# PV_Shutdown_2.net
KiCad netlist of a schematic drawn in Altium Designer
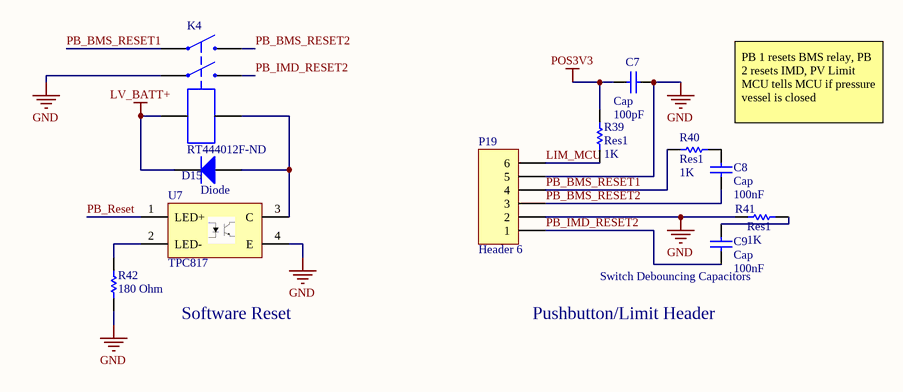
[diagram p0: PV_Shutdown_2.SchDoc]

(export (version "E")
  (design (tool "Eeschema 10.0.6"))
  (components
    (comp (ref "C7")
      (value "Cap")
      (footprint "1206")
      (description "Capacitor")
      (fields (field (name "ALTIUM_VALUE") "100pF") (field (name "PUBLISHER") "Altium Limited"))
      (libsource (lib "Miscellaneous Devices") (part "Cap"))
    )
    (comp (ref "C8")
      (value "Cap")
      (footprint "1206")
      (description "Capacitor")
      (fields (field (name "ALTIUM_VALUE") "100nF") (field (name "PUBLISHER") "Altium Limited"))
      (libsource (lib "Miscellaneous Devices") (part "Cap"))
    )
    (comp (ref "C9")
      (value "Cap")
      (footprint "1206")
      (description "Capacitor")
      (fields (field (name "ALTIUM_VALUE") "100nF") (field (name "PUBLISHER") "Altium Limited"))
      (libsource (lib "Miscellaneous Devices") (part "Cap"))
    )
    (comp (ref "D15")
      (value "Diode")
      (footprint "1N4007")
      (description "Default Diode")
      (fields (field (name "PUBLISHER") "Altium Limited"))
      (libsource (lib "Miscellaneous Devices") (part "Diode"))
    )
    (comp (ref "K4")
      (value "RT444012F-ND")
      (footprint "RT444012F")
      (description "RELAY GEN PURPOSE DPST 8A 12V")
      (libsource (lib "ic") (part "RT444012F-ND"))
    )
    (comp (ref "P19")
      (value "Header 6")
      (footprint "6POS TERM BLOCK")
      (description "Header, 6-Pin")
      (fields (field (name "PUBLISHER") "Altium Limited"))
      (libsource (lib "Miscellaneous Connectors") (part "Header 6"))
    )
    (comp (ref "R39")
      (value "Res1")
      (footprint "1206")
      (description "Resistor")
      (fields (field (name "ALTIUM_VALUE") "1K") (field (name "PUBLISHER") "Altium Limited"))
      (libsource (lib "Miscellaneous Devices") (part "Res1"))
    )
    (comp (ref "R40")
      (value "Res1")
      (footprint "1206")
      (description "Resistor")
      (fields (field (name "ALTIUM_VALUE") "1K") (field (name "PUBLISHER") "Altium Limited"))
      (libsource (lib "Miscellaneous Devices") (part "Res1"))
    )
    (comp (ref "R41")
      (value "Res1")
      (footprint "1206")
      (description "Resistor")
      (fields (field (name "ALTIUM_VALUE") "1K") (field (name "PUBLISHER") "Altium Limited"))
      (libsource (lib "Miscellaneous Devices") (part "Res1"))
    )
    (comp (ref "R42")
      (value "180 Ohm")
      (footprint "1206")
      (description "Resistor")
      (fields (field (name "Comment") "Res1") (field (name "PUBLISHER") "Altium Limited"))
      (libsource (lib "Miscellaneous Devices") (part "Res1"))
    )
    (comp (ref "U7")
      (value "TPC817")
      (footprint "4-SOP")
      (description "Opto-Coupler")
      (libsource (lib "ic") (part "TPC817"))
    )
  )
  (nets
    (net (code "1") (name "/LIM_MCU") (class "Default")
      (node (ref "P19") (pin "6") (pinfunction "6_6") (pintype "passive"))
      (node (ref "R39") (pin "1") (pinfunction "1_1") (pintype "passive"))
    )
    (net (code "2") (name "/PB_BMS_RESET1") (class "Default")
      (node (ref "K4") (pin "5") (pinfunction "5_5") (pintype "passive"))
      (node (ref "P19") (pin "4") (pinfunction "4_4") (pintype "passive"))
      (node (ref "R40") (pin "1") (pinfunction "1_1") (pintype "passive"))
    )
    (net (code "3") (name "/PB_BMS_RESET2") (class "Default")
      (node (ref "C8") (pin "1") (pinfunction "1_1") (pintype "passive"))
      (node (ref "K4") (pin "6") (pinfunction "6_6") (pintype "passive"))
      (node (ref "P19") (pin "3") (pinfunction "3_3") (pintype "passive"))
    )
    (net (code "4") (name "/PB_IMD_RESET2") (class "Default")
      (node (ref "C9") (pin "1") (pinfunction "1_1") (pintype "passive"))
      (node (ref "K4") (pin "4") (pinfunction "4_4") (pintype "passive"))
      (node (ref "P19") (pin "1") (pinfunction "1_1") (pintype "passive"))
    )
    (net (code "5") (name "/PB_Reset") (class "Default")
      (node (ref "U7") (pin "1") (pinfunction "LED+_1") (pintype "passive"))
    )
    (net (code "6") (name "GND") (class "Default")
      (node (ref "C7") (pin "1") (pinfunction "1_1") (pintype "passive"))
      (node (ref "K4") (pin "3") (pinfunction "3_3") (pintype "passive"))
      (node (ref "P19") (pin "2") (pinfunction "2_2") (pintype "passive"))
      (node (ref "P19") (pin "5") (pinfunction "5_5") (pintype "passive"))
      (node (ref "R41") (pin "1") (pinfunction "1_1") (pintype "passive"))
      (node (ref "R42") (pin "2") (pinfunction "2_2") (pintype "passive"))
      (node (ref "U7") (pin "4") (pinfunction "E_4") (pintype "passive"))
    )
    (net (code "7") (name "LV_BATT+") (class "Default")
      (node (ref "D15") (pin "2") (pinfunction "K_2") (pintype "passive"))
      (node (ref "K4") (pin "1") (pinfunction "1_1") (pintype "passive"))
    )
    (net (code "8") (name "Net-(C8-Pad2)") (class "Default")
      (node (ref "C8") (pin "2") (pinfunction "2_2") (pintype "passive"))
      (node (ref "R40") (pin "2") (pinfunction "2_2") (pintype "passive"))
    )
    (net (code "9") (name "Net-(C9-Pad2)") (class "Default")
      (node (ref "C9") (pin "2") (pinfunction "2_2") (pintype "passive"))
      (node (ref "R41") (pin "2") (pinfunction "2_2") (pintype "passive"))
    )
    (net (code "10") (name "Net-(D15-A)") (class "Default")
      (node (ref "D15") (pin "1") (pinfunction "A_1") (pintype "passive"))
      (node (ref "K4") (pin "2") (pinfunction "2_2") (pintype "passive"))
      (node (ref "U7") (pin "3") (pinfunction "C_3") (pintype "open_collector"))
    )
    (net (code "11") (name "Net-(U7-LED-)") (class "Default")
      (node (ref "R42") (pin "1") (pinfunction "1_1") (pintype "passive"))
      (node (ref "U7") (pin "2") (pinfunction "LED-_2") (pintype "open_emitter"))
    )
    (net (code "12") (name "POS3V3") (class "Default")
      (node (ref "C7") (pin "2") (pinfunction "2_2") (pintype "passive"))
      (node (ref "R39") (pin "2") (pinfunction "2_2") (pintype "passive"))
    )
  )
)
